# sensor_dan_converter.net
KiCad netlist of a schematic drawn in EAGLE
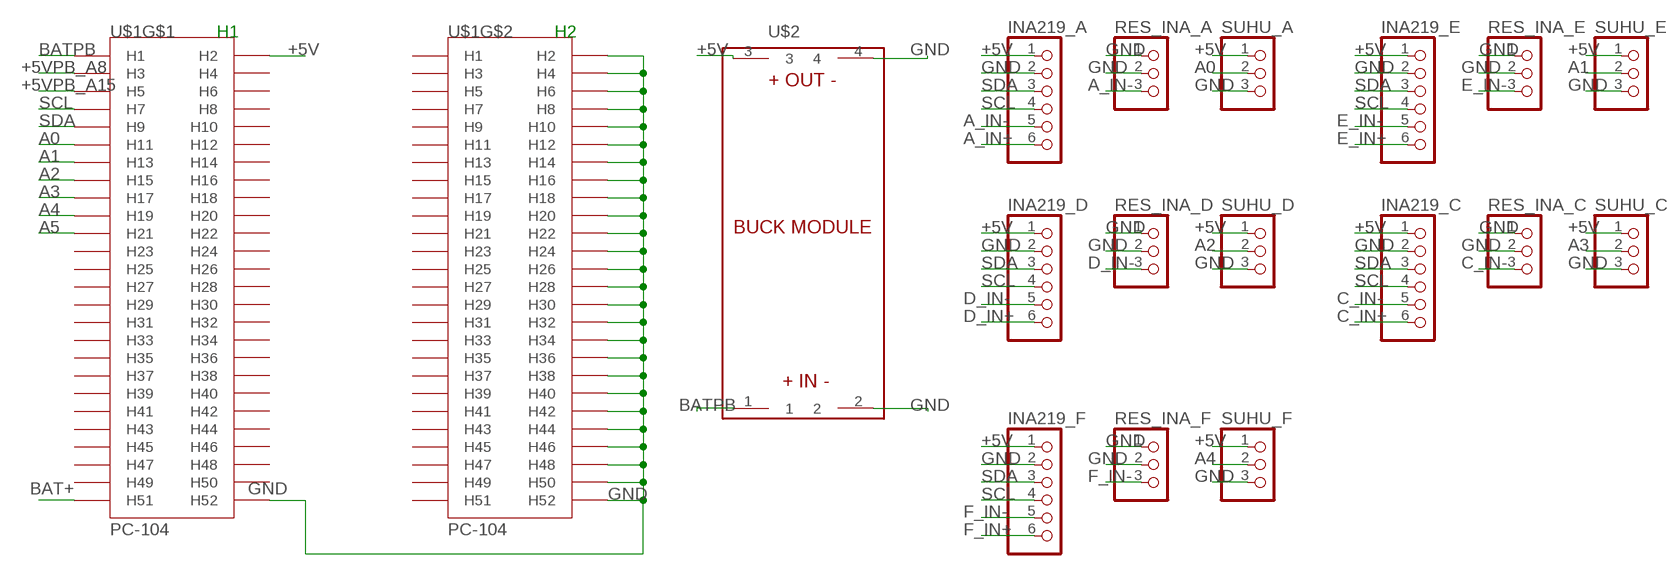
[diagram p0: schematic, sheet 1]

(export (version "E")
  (design (tool "Eeschema 10.0.6"))
  (components
    (comp (ref "INA219_A")
      (value "PINHD-1X6")
      (footprint "eagle-import:1X06")
      (libsource (lib "eagle-import") (part "PINHD-1X6"))
    )
    (comp (ref "INA219_C")
      (value "PINHD-1X6")
      (footprint "eagle-import:1X06")
      (libsource (lib "eagle-import") (part "PINHD-1X6"))
    )
    (comp (ref "INA219_D")
      (value "PINHD-1X6")
      (footprint "eagle-import:1X06")
      (libsource (lib "eagle-import") (part "PINHD-1X6"))
    )
    (comp (ref "INA219_E")
      (value "PINHD-1X6")
      (footprint "eagle-import:1X06")
      (libsource (lib "eagle-import") (part "PINHD-1X6"))
    )
    (comp (ref "INA219_F")
      (value "PINHD-1X6")
      (footprint "eagle-import:1X06")
      (libsource (lib "eagle-import") (part "PINHD-1X6"))
    )
    (comp (ref "RES_INA_A")
      (value "PINHD-1X3")
      (footprint "eagle-import:1X03")
      (libsource (lib "eagle-import") (part "PINHD-1X3"))
    )
    (comp (ref "RES_INA_C")
      (value "PINHD-1X3")
      (footprint "eagle-import:1X03")
      (libsource (lib "eagle-import") (part "PINHD-1X3"))
    )
    (comp (ref "RES_INA_D")
      (value "PINHD-1X3")
      (footprint "eagle-import:1X03")
      (libsource (lib "eagle-import") (part "PINHD-1X3"))
    )
    (comp (ref "RES_INA_E")
      (value "PINHD-1X3")
      (footprint "eagle-import:1X03")
      (libsource (lib "eagle-import") (part "PINHD-1X3"))
    )
    (comp (ref "RES_INA_F")
      (value "PINHD-1X3")
      (footprint "eagle-import:1X03")
      (libsource (lib "eagle-import") (part "PINHD-1X3"))
    )
    (comp (ref "SUHU_A")
      (value "PINHD-1X3")
      (footprint "eagle-import:1X03")
      (libsource (lib "eagle-import") (part "PINHD-1X3"))
    )
    (comp (ref "SUHU_C")
      (value "PINHD-1X3")
      (footprint "eagle-import:1X03")
      (libsource (lib "eagle-import") (part "PINHD-1X3"))
    )
    (comp (ref "SUHU_D")
      (value "PINHD-1X3")
      (footprint "eagle-import:1X03")
      (libsource (lib "eagle-import") (part "PINHD-1X3"))
    )
    (comp (ref "SUHU_E")
      (value "PINHD-1X3")
      (footprint "eagle-import:1X03")
      (libsource (lib "eagle-import") (part "PINHD-1X3"))
    )
    (comp (ref "SUHU_F")
      (value "PINHD-1X3")
      (footprint "eagle-import:1X03")
      (libsource (lib "eagle-import") (part "PINHD-1X3"))
    )
    (comp (ref "U$1")
      (value "PC-104")
      (footprint "eagle-import:PC-104")
      (libsource (lib "eagle-import") (part "PC-104"))
    )
    (comp (ref "U$2")
      (value "BUCK_MODULEWITH_SMDPADS&THROUGHHOLES")
      (footprint "eagle-import:BUCK_MODULE")
      (libsource (lib "eagle-import") (part "BUCK_MODULEWITH_SMDPADS&THROUGHHOLES"))
    )
  )
  (nets
    (net (code "1") (name "/+5V") (class "Default")
      (node (ref "INA219_A") (pin "1") (pinfunction "1_1") (pintype "passive"))
      (node (ref "INA219_C") (pin "1") (pinfunction "1_1") (pintype "passive"))
      (node (ref "INA219_D") (pin "1") (pinfunction "1_1") (pintype "passive"))
      (node (ref "INA219_E") (pin "1") (pinfunction "1_1") (pintype "passive"))
      (node (ref "INA219_F") (pin "1") (pinfunction "1_1") (pintype "passive"))
      (node (ref "SUHU_A") (pin "1") (pinfunction "1_1") (pintype "passive"))
      (node (ref "SUHU_C") (pin "1") (pinfunction "1_1") (pintype "passive"))
      (node (ref "SUHU_D") (pin "1") (pinfunction "1_1") (pintype "passive"))
      (node (ref "SUHU_E") (pin "1") (pinfunction "1_1") (pintype "passive"))
      (node (ref "SUHU_F") (pin "1") (pinfunction "1_1") (pintype "passive"))
      (node (ref "U$1") (pin "P$2") (pinfunction "H2_P$2") (pintype "bidirectional"))
      (node (ref "U$2") (pin "3") (pinfunction "3_3") (pintype "bidirectional"))
    )
    (net (code "2") (name "/+5VPB_A8") (class "Default")
      (node (ref "U$1") (pin "P$3") (pinfunction "H3_P$3") (pintype "bidirectional"))
    )
    (net (code "3") (name "/+5VPB_A15") (class "Default")
      (node (ref "U$1") (pin "P$5") (pinfunction "H5_P$5") (pintype "bidirectional"))
    )
    (net (code "4") (name "/A0") (class "Default")
      (node (ref "SUHU_A") (pin "2") (pinfunction "2_2") (pintype "passive"))
      (node (ref "U$1") (pin "P$11") (pinfunction "H11_P$11") (pintype "bidirectional"))
    )
    (net (code "5") (name "/A1") (class "Default")
      (node (ref "SUHU_E") (pin "2") (pinfunction "2_2") (pintype "passive"))
      (node (ref "U$1") (pin "P$13") (pinfunction "H13_P$13") (pintype "bidirectional"))
    )
    (net (code "6") (name "/A2") (class "Default")
      (node (ref "SUHU_D") (pin "2") (pinfunction "2_2") (pintype "passive"))
      (node (ref "U$1") (pin "P$15") (pinfunction "H15_P$15") (pintype "bidirectional"))
    )
    (net (code "7") (name "/A3") (class "Default")
      (node (ref "SUHU_C") (pin "2") (pinfunction "2_2") (pintype "passive"))
      (node (ref "U$1") (pin "P$17") (pinfunction "H17_P$17") (pintype "bidirectional"))
    )
    (net (code "8") (name "/A4") (class "Default")
      (node (ref "SUHU_F") (pin "2") (pinfunction "2_2") (pintype "passive"))
      (node (ref "U$1") (pin "P$19") (pinfunction "H19_P$19") (pintype "bidirectional"))
    )
    (net (code "9") (name "/A5") (class "Default")
      (node (ref "U$1") (pin "P$21") (pinfunction "H21_P$21") (pintype "bidirectional"))
    )
    (net (code "10") (name "/A_IN+") (class "Default")
      (node (ref "INA219_A") (pin "6") (pinfunction "6_6") (pintype "passive"))
    )
    (net (code "11") (name "/A_IN-") (class "Default")
      (node (ref "INA219_A") (pin "5") (pinfunction "5_5") (pintype "passive"))
      (node (ref "RES_INA_A") (pin "3") (pinfunction "3_3") (pintype "passive"))
    )
    (net (code "12") (name "/BAT+") (class "Default")
      (node (ref "U$1") (pin "P$51") (pinfunction "H51_P$51") (pintype "bidirectional"))
    )
    (net (code "13") (name "/BATPB") (class "Default")
      (node (ref "U$1") (pin "P$1") (pinfunction "H1_P$1") (pintype "bidirectional"))
      (node (ref "U$2") (pin "1") (pinfunction "1_1") (pintype "bidirectional"))
    )
    (net (code "14") (name "/C_IN+") (class "Default")
      (node (ref "INA219_C") (pin "6") (pinfunction "6_6") (pintype "passive"))
    )
    (net (code "15") (name "/C_IN-") (class "Default")
      (node (ref "INA219_C") (pin "5") (pinfunction "5_5") (pintype "passive"))
      (node (ref "RES_INA_C") (pin "3") (pinfunction "3_3") (pintype "passive"))
    )
    (net (code "16") (name "/D_IN+") (class "Default")
      (node (ref "INA219_D") (pin "6") (pinfunction "6_6") (pintype "passive"))
    )
    (net (code "17") (name "/D_IN-") (class "Default")
      (node (ref "INA219_D") (pin "5") (pinfunction "5_5") (pintype "passive"))
      (node (ref "RES_INA_D") (pin "3") (pinfunction "3_3") (pintype "passive"))
    )
    (net (code "18") (name "/E_IN+") (class "Default")
      (node (ref "INA219_E") (pin "6") (pinfunction "6_6") (pintype "passive"))
    )
    (net (code "19") (name "/E_IN-") (class "Default")
      (node (ref "INA219_E") (pin "5") (pinfunction "5_5") (pintype "passive"))
      (node (ref "RES_INA_E") (pin "3") (pinfunction "3_3") (pintype "passive"))
    )
    (net (code "20") (name "/F_IN+") (class "Default")
      (node (ref "INA219_F") (pin "6") (pinfunction "6_6") (pintype "passive"))
    )
    (net (code "21") (name "/F_IN-") (class "Default")
      (node (ref "INA219_F") (pin "5") (pinfunction "5_5") (pintype "passive"))
      (node (ref "RES_INA_F") (pin "3") (pinfunction "3_3") (pintype "passive"))
    )
    (net (code "22") (name "/GND") (class "Default")
      (node (ref "INA219_A") (pin "2") (pinfunction "2_2") (pintype "passive"))
      (node (ref "INA219_C") (pin "2") (pinfunction "2_2") (pintype "passive"))
      (node (ref "INA219_D") (pin "2") (pinfunction "2_2") (pintype "passive"))
      (node (ref "INA219_E") (pin "2") (pinfunction "2_2") (pintype "passive"))
      (node (ref "INA219_F") (pin "2") (pinfunction "2_2") (pintype "passive"))
      (node (ref "RES_INA_A") (pin "1") (pinfunction "1_1") (pintype "passive"))
      (node (ref "RES_INA_A") (pin "2") (pinfunction "2_2") (pintype "passive"))
      (node (ref "RES_INA_C") (pin "1") (pinfunction "1_1") (pintype "passive"))
      (node (ref "RES_INA_C") (pin "2") (pinfunction "2_2") (pintype "passive"))
      (node (ref "RES_INA_D") (pin "1") (pinfunction "1_1") (pintype "passive"))
      (node (ref "RES_INA_D") (pin "2") (pinfunction "2_2") (pintype "passive"))
      (node (ref "RES_INA_E") (pin "1") (pinfunction "1_1") (pintype "passive"))
      (node (ref "RES_INA_E") (pin "2") (pinfunction "2_2") (pintype "passive"))
      (node (ref "RES_INA_F") (pin "1") (pinfunction "1_1") (pintype "passive"))
      (node (ref "RES_INA_F") (pin "2") (pinfunction "2_2") (pintype "passive"))
      (node (ref "SUHU_A") (pin "3") (pinfunction "3_3") (pintype "passive"))
      (node (ref "SUHU_C") (pin "3") (pinfunction "3_3") (pintype "passive"))
      (node (ref "SUHU_D") (pin "3") (pinfunction "3_3") (pintype "passive"))
      (node (ref "SUHU_E") (pin "3") (pinfunction "3_3") (pintype "passive"))
      (node (ref "SUHU_F") (pin "3") (pinfunction "3_3") (pintype "passive"))
      (node (ref "U$1") (pin "P$100") (pinfunction "H48_P$100") (pintype "bidirectional"))
      (node (ref "U$1") (pin "P$102") (pinfunction "H50_P$102") (pintype "bidirectional"))
      (node (ref "U$1") (pin "P$104") (pinfunction "H52_P$104") (pintype "bidirectional"))
      (node (ref "U$1") (pin "P$52") (pinfunction "H52_P$52") (pintype "bidirectional"))
      (node (ref "U$1") (pin "P$54") (pinfunction "H2_P$54") (pintype "bidirectional"))
      (node (ref "U$1") (pin "P$56") (pinfunction "H4_P$56") (pintype "bidirectional"))
      (node (ref "U$1") (pin "P$58") (pinfunction "H6_P$58") (pintype "bidirectional"))
      (node (ref "U$1") (pin "P$60") (pinfunction "H8_P$60") (pintype "bidirectional"))
      (node (ref "U$1") (pin "P$62") (pinfunction "H10_P$62") (pintype "bidirectional"))
      (node (ref "U$1") (pin "P$64") (pinfunction "H12_P$64") (pintype "bidirectional"))
      (node (ref "U$1") (pin "P$66") (pinfunction "H14_P$66") (pintype "bidirectional"))
      (node (ref "U$1") (pin "P$68") (pinfunction "H16_P$68") (pintype "bidirectional"))
      (node (ref "U$1") (pin "P$70") (pinfunction "H18_P$70") (pintype "bidirectional"))
      (node (ref "U$1") (pin "P$72") (pinfunction "H20_P$72") (pintype "bidirectional"))
      (node (ref "U$1") (pin "P$74") (pinfunction "H22_P$74") (pintype "bidirectional"))
      (node (ref "U$1") (pin "P$76") (pinfunction "H24_P$76") (pintype "bidirectional"))
      (node (ref "U$1") (pin "P$78") (pinfunction "H26_P$78") (pintype "bidirectional"))
      (node (ref "U$1") (pin "P$80") (pinfunction "H28_P$80") (pintype "bidirectional"))
      (node (ref "U$1") (pin "P$82") (pinfunction "H30_P$82") (pintype "bidirectional"))
      (node (ref "U$1") (pin "P$84") (pinfunction "H32_P$84") (pintype "bidirectional"))
      (node (ref "U$1") (pin "P$86") (pinfunction "H34_P$86") (pintype "bidirectional"))
      (node (ref "U$1") (pin "P$88") (pinfunction "H36_P$88") (pintype "bidirectional"))
      (node (ref "U$1") (pin "P$90") (pinfunction "H38_P$90") (pintype "bidirectional"))
      (node (ref "U$1") (pin "P$92") (pinfunction "H40_P$92") (pintype "bidirectional"))
      (node (ref "U$1") (pin "P$94") (pinfunction "H42_P$94") (pintype "bidirectional"))
      (node (ref "U$1") (pin "P$96") (pinfunction "H44_P$96") (pintype "bidirectional"))
      (node (ref "U$1") (pin "P$98") (pinfunction "H46_P$98") (pintype "bidirectional"))
      (node (ref "U$2") (pin "2") (pinfunction "2_2") (pintype "bidirectional"))
      (node (ref "U$2") (pin "4") (pinfunction "4_4") (pintype "bidirectional"))
    )
    (net (code "23") (name "/SCL") (class "Default")
      (node (ref "INA219_A") (pin "4") (pinfunction "4_4") (pintype "passive"))
      (node (ref "INA219_C") (pin "4") (pinfunction "4_4") (pintype "passive"))
      (node (ref "INA219_D") (pin "4") (pinfunction "4_4") (pintype "passive"))
      (node (ref "INA219_E") (pin "4") (pinfunction "4_4") (pintype "passive"))
      (node (ref "INA219_F") (pin "4") (pinfunction "4_4") (pintype "passive"))
      (node (ref "U$1") (pin "P$7") (pinfunction "H7_P$7") (pintype "bidirectional"))
    )
    (net (code "24") (name "/SDA") (class "Default")
      (node (ref "INA219_A") (pin "3") (pinfunction "3_3") (pintype "passive"))
      (node (ref "INA219_C") (pin "3") (pinfunction "3_3") (pintype "passive"))
      (node (ref "INA219_D") (pin "3") (pinfunction "3_3") (pintype "passive"))
      (node (ref "INA219_E") (pin "3") (pinfunction "3_3") (pintype "passive"))
      (node (ref "INA219_F") (pin "3") (pinfunction "3_3") (pintype "passive"))
      (node (ref "U$1") (pin "P$9") (pinfunction "H9_P$9") (pintype "bidirectional"))
    )
    (net (code "25") (name "unconnected-(U$1A-H4-PadP$4)") (class "Default")
      (node (ref "U$1") (pin "P$4") (pinfunction "H4_P$4") (pintype "bidirectional"))
    )
    (net (code "26") (name "unconnected-(U$1A-H6-PadP$6)") (class "Default")
      (node (ref "U$1") (pin "P$6") (pinfunction "H6_P$6") (pintype "bidirectional"))
    )
    (net (code "27") (name "unconnected-(U$1A-H8-PadP$8)") (class "Default")
      (node (ref "U$1") (pin "P$8") (pinfunction "H8_P$8") (pintype "bidirectional"))
    )
    (net (code "28") (name "unconnected-(U$1A-H10-PadP$10)") (class "Default")
      (node (ref "U$1") (pin "P$10") (pinfunction "H10_P$10") (pintype "bidirectional"))
    )
    (net (code "29") (name "unconnected-(U$1A-H12-PadP$12)") (class "Default")
      (node (ref "U$1") (pin "P$12") (pinfunction "H12_P$12") (pintype "bidirectional"))
    )
    (net (code "30") (name "unconnected-(U$1A-H14-PadP$14)") (class "Default")
      (node (ref "U$1") (pin "P$14") (pinfunction "H14_P$14") (pintype "bidirectional"))
    )
    (net (code "31") (name "unconnected-(U$1A-H16-PadP$16)") (class "Default")
      (node (ref "U$1") (pin "P$16") (pinfunction "H16_P$16") (pintype "bidirectional"))
    )
    (net (code "32") (name "unconnected-(U$1A-H18-PadP$18)") (class "Default")
      (node (ref "U$1") (pin "P$18") (pinfunction "H18_P$18") (pintype "bidirectional"))
    )
    (net (code "33") (name "unconnected-(U$1A-H20-PadP$20)") (class "Default")
      (node (ref "U$1") (pin "P$20") (pinfunction "H20_P$20") (pintype "bidirectional"))
    )
    (net (code "34") (name "unconnected-(U$1A-H22-PadP$22)") (class "Default")
      (node (ref "U$1") (pin "P$22") (pinfunction "H22_P$22") (pintype "bidirectional"))
    )
    (net (code "35") (name "unconnected-(U$1A-H23-PadP$23)") (class "Default")
      (node (ref "U$1") (pin "P$23") (pinfunction "H23_P$23") (pintype "bidirectional"))
    )
    (net (code "36") (name "unconnected-(U$1A-H24-PadP$24)") (class "Default")
      (node (ref "U$1") (pin "P$24") (pinfunction "H24_P$24") (pintype "bidirectional"))
    )
    (net (code "37") (name "unconnected-(U$1A-H25-PadP$25)") (class "Default")
      (node (ref "U$1") (pin "P$25") (pinfunction "H25_P$25") (pintype "bidirectional"))
    )
    (net (code "38") (name "unconnected-(U$1A-H26-PadP$26)") (class "Default")
      (node (ref "U$1") (pin "P$26") (pinfunction "H26_P$26") (pintype "bidirectional"))
    )
    (net (code "39") (name "unconnected-(U$1A-H27-PadP$27)") (class "Default")
      (node (ref "U$1") (pin "P$27") (pinfunction "H27_P$27") (pintype "bidirectional"))
    )
    (net (code "40") (name "unconnected-(U$1A-H28-PadP$28)") (class "Default")
      (node (ref "U$1") (pin "P$28") (pinfunction "H28_P$28") (pintype "bidirectional"))
    )
    (net (code "41") (name "unconnected-(U$1A-H29-PadP$29)") (class "Default")
      (node (ref "U$1") (pin "P$29") (pinfunction "H29_P$29") (pintype "bidirectional"))
    )
    (net (code "42") (name "unconnected-(U$1A-H30-PadP$30)") (class "Default")
      (node (ref "U$1") (pin "P$30") (pinfunction "H30_P$30") (pintype "bidirectional"))
    )
    (net (code "43") (name "unconnected-(U$1A-H31-PadP$31)") (class "Default")
      (node (ref "U$1") (pin "P$31") (pinfunction "H31_P$31") (pintype "bidirectional"))
    )
    (net (code "44") (name "unconnected-(U$1A-H32-PadP$32)") (class "Default")
      (node (ref "U$1") (pin "P$32") (pinfunction "H32_P$32") (pintype "bidirectional"))
    )
    (net (code "45") (name "unconnected-(U$1A-H33-PadP$33)") (class "Default")
      (node (ref "U$1") (pin "P$33") (pinfunction "H33_P$33") (pintype "bidirectional"))
    )
    (net (code "46") (name "unconnected-(U$1A-H34-PadP$34)") (class "Default")
      (node (ref "U$1") (pin "P$34") (pinfunction "H34_P$34") (pintype "bidirectional"))
    )
    (net (code "47") (name "unconnected-(U$1A-H35-PadP$35)") (class "Default")
      (node (ref "U$1") (pin "P$35") (pinfunction "H35_P$35") (pintype "bidirectional"))
    )
    (net (code "48") (name "unconnected-(U$1A-H36-PadP$36)") (class "Default")
      (node (ref "U$1") (pin "P$36") (pinfunction "H36_P$36") (pintype "bidirectional"))
    )
    (net (code "49") (name "unconnected-(U$1A-H37-PadP$37)") (class "Default")
      (node (ref "U$1") (pin "P$37") (pinfunction "H37_P$37") (pintype "bidirectional"))
    )
    (net (code "50") (name "unconnected-(U$1A-H38-PadP$38)") (class "Default")
      (node (ref "U$1") (pin "P$38") (pinfunction "H38_P$38") (pintype "bidirectional"))
    )
    (net (code "51") (name "unconnected-(U$1A-H39-PadP$39)") (class "Default")
      (node (ref "U$1") (pin "P$39") (pinfunction "H39_P$39") (pintype "bidirectional"))
    )
    (net (code "52") (name "unconnected-(U$1A-H40-PadP$40)") (class "Default")
      (node (ref "U$1") (pin "P$40") (pinfunction "H40_P$40") (pintype "bidirectional"))
    )
    (net (code "53") (name "unconnected-(U$1A-H41-PadP$41)") (class "Default")
      (node (ref "U$1") (pin "P$41") (pinfunction "H41_P$41") (pintype "bidirectional"))
    )
    (net (code "54") (name "unconnected-(U$1A-H42-PadP$42)") (class "Default")
      (node (ref "U$1") (pin "P$42") (pinfunction "H42_P$42") (pintype "bidirectional"))
    )
    (net (code "55") (name "unconnected-(U$1A-H43-PadP$43)") (class "Default")
      (node (ref "U$1") (pin "P$43") (pinfunction "H43_P$43") (pintype "bidirectional"))
    )
    (net (code "56") (name "unconnected-(U$1A-H44-PadP$44)") (class "Default")
      (node (ref "U$1") (pin "P$44") (pinfunction "H44_P$44") (pintype "bidirectional"))
    )
    (net (code "57") (name "unconnected-(U$1A-H45-PadP$45)") (class "Default")
      (node (ref "U$1") (pin "P$45") (pinfunction "H45_P$45") (pintype "bidirectional"))
    )
    (net (code "58") (name "unconnected-(U$1A-H46-PadP$46)") (class "Default")
      (node (ref "U$1") (pin "P$46") (pinfunction "H46_P$46") (pintype "bidirectional"))
    )
    (net (code "59") (name "unconnected-(U$1A-H47-PadP$47)") (class "Default")
      (node (ref "U$1") (pin "P$47") (pinfunction "H47_P$47") (pintype "bidirectional"))
    )
    (net (code "60") (name "unconnected-(U$1A-H48-PadP$48)") (class "Default")
      (node (ref "U$1") (pin "P$48") (pinfunction "H48_P$48") (pintype "bidirectional"))
    )
    (net (code "61") (name "unconnected-(U$1A-H49-PadP$49)") (class "Default")
      (node (ref "U$1") (pin "P$49") (pinfunction "H49_P$49") (pintype "bidirectional"))
    )
    (net (code "62") (name "unconnected-(U$1A-H50-PadP$50)") (class "Default")
      (node (ref "U$1") (pin "P$50") (pinfunction "H50_P$50") (pintype "bidirectional"))
    )
    (net (code "63") (name "unconnected-(U$1B-H1-PadP$53)") (class "Default")
      (node (ref "U$1") (pin "P$53") (pinfunction "H1_P$53") (pintype "bidirectional"))
    )
    (net (code "64") (name "unconnected-(U$1B-H3-PadP$55)") (class "Default")
      (node (ref "U$1") (pin "P$55") (pinfunction "H3_P$55") (pintype "bidirectional"))
    )
    (net (code "65") (name "unconnected-(U$1B-H5-PadP$57)") (class "Default")
      (node (ref "U$1") (pin "P$57") (pinfunction "H5_P$57") (pintype "bidirectional"))
    )
    (net (code "66") (name "unconnected-(U$1B-H7-PadP$59)") (class "Default")
      (node (ref "U$1") (pin "P$59") (pinfunction "H7_P$59") (pintype "bidirectional"))
    )
    (net (code "67") (name "unconnected-(U$1B-H9-PadP$61)") (class "Default")
      (node (ref "U$1") (pin "P$61") (pinfunction "H9_P$61") (pintype "bidirectional"))
    )
    (net (code "68") (name "unconnected-(U$1B-H11-PadP$63)") (class "Default")
      (node (ref "U$1") (pin "P$63") (pinfunction "H11_P$63") (pintype "bidirectional"))
    )
    (net (code "69") (name "unconnected-(U$1B-H13-PadP$65)") (class "Default")
      (node (ref "U$1") (pin "P$65") (pinfunction "H13_P$65") (pintype "bidirectional"))
    )
    (net (code "70") (name "unconnected-(U$1B-H15-PadP$67)") (class "Default")
      (node (ref "U$1") (pin "P$67") (pinfunction "H15_P$67") (pintype "bidirectional"))
    )
    (net (code "71") (name "unconnected-(U$1B-H17-PadP$69)") (class "Default")
      (node (ref "U$1") (pin "P$69") (pinfunction "H17_P$69") (pintype "bidirectional"))
    )
    (net (code "72") (name "unconnected-(U$1B-H19-PadP$71)") (class "Default")
      (node (ref "U$1") (pin "P$71") (pinfunction "H19_P$71") (pintype "bidirectional"))
    )
    (net (code "73") (name "unconnected-(U$1B-H21-PadP$73)") (class "Default")
      (node (ref "U$1") (pin "P$73") (pinfunction "H21_P$73") (pintype "bidirectional"))
    )
    (net (code "74") (name "unconnected-(U$1B-H23-PadP$75)") (class "Default")
      (node (ref "U$1") (pin "P$75") (pinfunction "H23_P$75") (pintype "bidirectional"))
    )
    (net (code "75") (name "unconnected-(U$1B-H25-PadP$77)") (class "Default")
      (node (ref "U$1") (pin "P$77") (pinfunction "H25_P$77") (pintype "bidirectional"))
    )
    (net (code "76") (name "unconnected-(U$1B-H27-PadP$79)") (class "Default")
      (node (ref "U$1") (pin "P$79") (pinfunction "H27_P$79") (pintype "bidirectional"))
    )
    (net (code "77") (name "unconnected-(U$1B-H29-PadP$81)") (class "Default")
      (node (ref "U$1") (pin "P$81") (pinfunction "H29_P$81") (pintype "bidirectional"))
    )
    (net (code "78") (name "unconnected-(U$1B-H31-PadP$83)") (class "Default")
      (node (ref "U$1") (pin "P$83") (pinfunction "H31_P$83") (pintype "bidirectional"))
    )
    (net (code "79") (name "unconnected-(U$1B-H33-PadP$85)") (class "Default")
      (node (ref "U$1") (pin "P$85") (pinfunction "H33_P$85") (pintype "bidirectional"))
    )
    (net (code "80") (name "unconnected-(U$1B-H35-PadP$87)") (class "Default")
      (node (ref "U$1") (pin "P$87") (pinfunction "H35_P$87") (pintype "bidirectional"))
    )
    (net (code "81") (name "unconnected-(U$1B-H37-PadP$89)") (class "Default")
      (node (ref "U$1") (pin "P$89") (pinfunction "H37_P$89") (pintype "bidirectional"))
    )
    (net (code "82") (name "unconnected-(U$1B-H39-PadP$91)") (class "Default")
      (node (ref "U$1") (pin "P$91") (pinfunction "H39_P$91") (pintype "bidirectional"))
    )
    (net (code "83") (name "unconnected-(U$1B-H41-PadP$93)") (class "Default")
      (node (ref "U$1") (pin "P$93") (pinfunction "H41_P$93") (pintype "bidirectional"))
    )
    (net (code "84") (name "unconnected-(U$1B-H43-PadP$95)") (class "Default")
      (node (ref "U$1") (pin "P$95") (pinfunction "H43_P$95") (pintype "bidirectional"))
    )
    (net (code "85") (name "unconnected-(U$1B-H45-PadP$97)") (class "Default")
      (node (ref "U$1") (pin "P$97") (pinfunction "H45_P$97") (pintype "bidirectional"))
    )
    (net (code "86") (name "unconnected-(U$1B-H47-PadP$99)") (class "Default")
      (node (ref "U$1") (pin "P$99") (pinfunction "H47_P$99") (pintype "bidirectional"))
    )
    (net (code "87") (name "unconnected-(U$1B-H49-PadP$101)") (class "Default")
      (node (ref "U$1") (pin "P$101") (pinfunction "H49_P$101") (pintype "bidirectional"))
    )
    (net (code "88") (name "unconnected-(U$1B-H51-PadP$103)") (class "Default")
      (node (ref "U$1") (pin "P$103") (pinfunction "H51_P$103") (pintype "bidirectional"))
    )
  )
)
